# PHONE.net
KiCad netlist of a schematic drawn in EAGLE
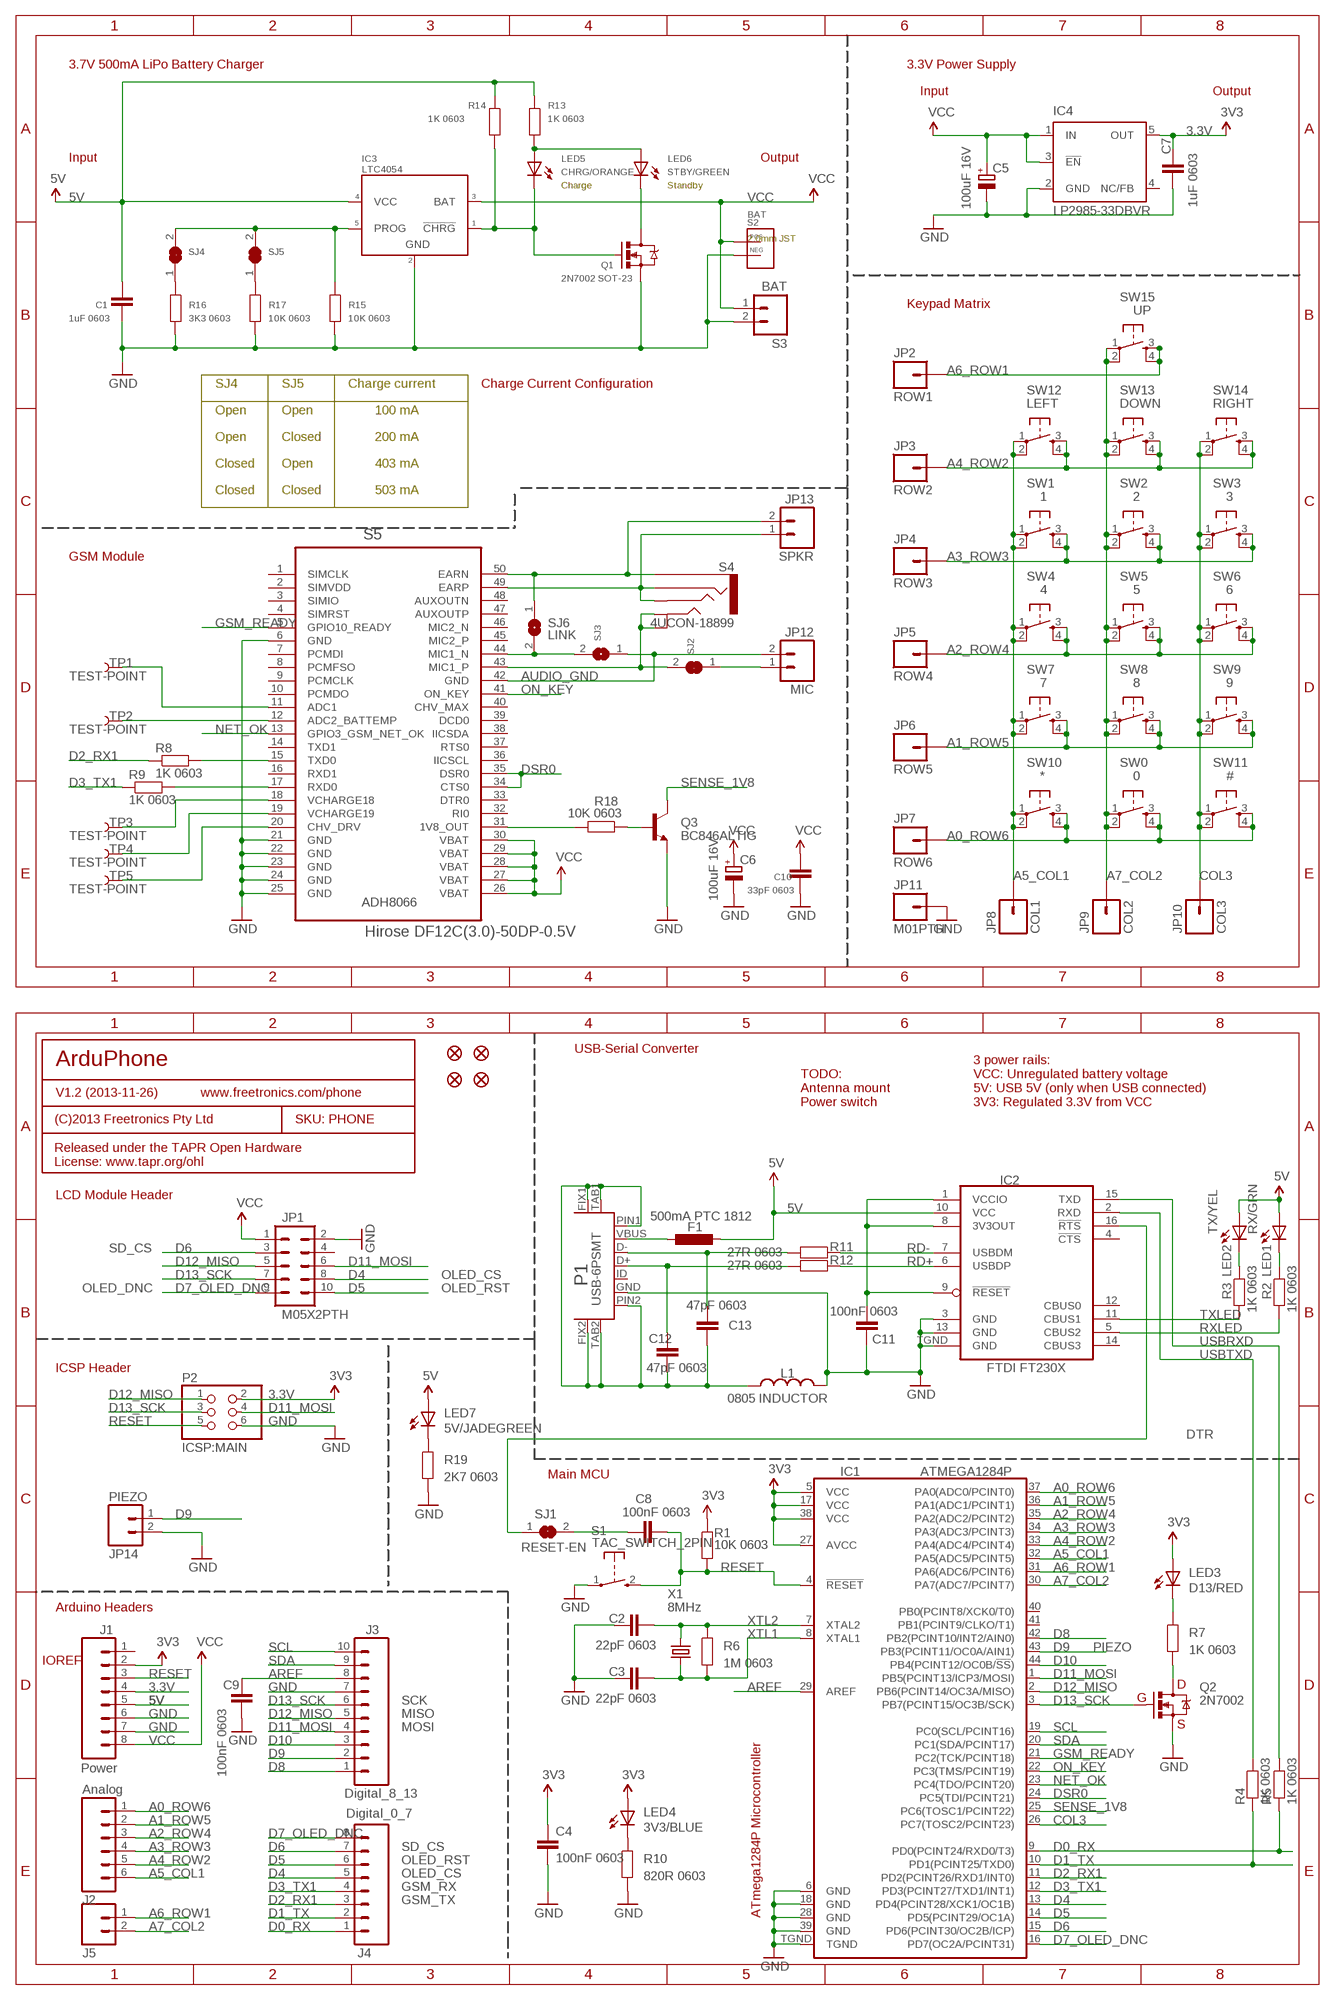
[diagram p0: schematic, sheet 1]

(export (version "E")
  (design (tool "Eeschema 10.0.6"))
  (components
    (comp (ref "C1")
      (value "1uF 0603")
      (footprint "eagle-import:0603")
      (libsource (lib "eagle-import") (part "freetronics-master-v1.1_CAP0603"))
    )
    (comp (ref "C2")
      (value "22pF 0603")
      (footprint "eagle-import:0603")
      (libsource (lib "eagle-import") (part "freetronics-master-v1.1_CAP0603"))
    )
    (comp (ref "C3")
      (value "22pF 0603")
      (footprint "eagle-import:0603")
      (libsource (lib "eagle-import") (part "freetronics-master-v1.1_CAP0603"))
    )
    (comp (ref "C4")
      (value "100nF 0603")
      (footprint "eagle-import:0603")
      (libsource (lib "eagle-import") (part "freetronics-master-v1.1_CAP0603"))
    )
    (comp (ref "C5")
      (value "100uF 16V")
      (footprint "eagle-import:PANASONIC_D")
      (libsource (lib "eagle-import") (part "CPOL-EUD"))
    )
    (comp (ref "C6")
      (value "100uF 16V")
      (footprint "eagle-import:PANASONIC_D")
      (libsource (lib "eagle-import") (part "CPOL-EUD"))
    )
    (comp (ref "C7")
      (value "1uF 0603")
      (footprint "eagle-import:0603")
      (libsource (lib "eagle-import") (part "freetronics-master-v1.1_CAP0603"))
    )
    (comp (ref "C8")
      (value "100nF 0603")
      (footprint "eagle-import:0603")
      (libsource (lib "eagle-import") (part "freetronics-master-v1.1_CAP0603"))
    )
    (comp (ref "C9")
      (value "100nF 0603")
      (footprint "eagle-import:0603")
      (libsource (lib "eagle-import") (part "freetronics-master-v1.1_CAP0603"))
    )
    (comp (ref "C10")
      (value "33pF 0603")
      (footprint "eagle-import:0603@1")
      (libsource (lib "eagle-import") (part "CAP0603"))
    )
    (comp (ref "C11")
      (value "100nF 0603")
      (footprint "eagle-import:0603")
      (libsource (lib "eagle-import") (part "freetronics-master-v1.1_CAP0603"))
    )
    (comp (ref "C12")
      (value "47pF 0603")
      (footprint "eagle-import:C0603")
      (libsource (lib "eagle-import") (part "C-EUC0603"))
    )
    (comp (ref "C13")
      (value "47pF 0603")
      (footprint "eagle-import:C0603")
      (libsource (lib "eagle-import") (part "C-EUC0603"))
    )
    (comp (ref "F1")
      (value "500mA PTC 1812")
      (footprint "eagle-import:L1812")
      (libsource (lib "eagle-import") (part "L-EUL1812"))
    )
    (comp (ref "IC1")
      (value "ATMEGA1284P")
      (footprint "eagle-import:QFN-44M1")
      (libsource (lib "eagle-import") (part "ATMEGA1284P"))
    )
    (comp (ref "IC2")
      (value "FT230X")
      (footprint "eagle-import:QFN-16")
      (libsource (lib "eagle-import") (part "FT230X"))
    )
    (comp (ref "IC3")
      (value "LTC4054")
      (footprint "eagle-import:SOT23-5")
      (libsource (lib "eagle-import") (part "LTC4054"))
    )
    (comp (ref "IC4")
      (value "LP2985-33DBVR")
      (footprint "eagle-import:TEXAS_SOT23-DBV")
      (libsource (lib "eagle-import") (part "TEXAS_TPS77033"))
    )
    (comp (ref "J1")
      (value "Power")
      (footprint "eagle-import:1X08")
      (libsource (lib "eagle-import") (part "M08"))
    )
    (comp (ref "J2")
      (value "Analog")
      (footprint "eagle-import:1X06")
      (libsource (lib "eagle-import") (part "M06SIP"))
    )
    (comp (ref "J3")
      (value "Digital_8_13")
      (footprint "eagle-import:1X10")
      (libsource (lib "eagle-import") (part "M100.1"))
    )
    (comp (ref "J4")
      (value "Digital_0_7")
      (footprint "eagle-import:1X08")
      (libsource (lib "eagle-import") (part "M08"))
    )
    (comp (ref "J5")
      (value "M02PTH")
      (footprint "eagle-import:1X02")
      (libsource (lib "eagle-import") (part "M02PTH"))
    )
    (comp (ref "JP1")
      (value "M05X2PTH")
      (footprint "eagle-import:AVR_ICSP")
      (libsource (lib "eagle-import") (part "M05X2PTH"))
    )
    (comp (ref "JP2")
      (value "ROW1")
      (footprint "eagle-import:1X01")
      (libsource (lib "eagle-import") (part "M01PTH"))
    )
    (comp (ref "JP3")
      (value "ROW2")
      (footprint "eagle-import:1X01")
      (libsource (lib "eagle-import") (part "M01PTH"))
    )
    (comp (ref "JP4")
      (value "ROW3")
      (footprint "eagle-import:1X01")
      (libsource (lib "eagle-import") (part "M01PTH"))
    )
    (comp (ref "JP5")
      (value "ROW4")
      (footprint "eagle-import:1X01")
      (libsource (lib "eagle-import") (part "M01PTH"))
    )
    (comp (ref "JP6")
      (value "ROW5")
      (footprint "eagle-import:1X01")
      (libsource (lib "eagle-import") (part "M01PTH"))
    )
    (comp (ref "JP7")
      (value "ROW6")
      (footprint "eagle-import:1X01")
      (libsource (lib "eagle-import") (part "M01PTH"))
    )
    (comp (ref "JP8")
      (value "COL1")
      (footprint "eagle-import:1X01")
      (libsource (lib "eagle-import") (part "M01PTH"))
    )
    (comp (ref "JP9")
      (value "COL2")
      (footprint "eagle-import:1X01")
      (libsource (lib "eagle-import") (part "M01PTH"))
    )
    (comp (ref "JP10")
      (value "COL3")
      (footprint "eagle-import:1X01")
      (libsource (lib "eagle-import") (part "M01PTH"))
    )
    (comp (ref "JP11")
      (value "M01PTH")
      (footprint "eagle-import:1X01")
      (libsource (lib "eagle-import") (part "freetronics-original_M01PTH"))
    )
    (comp (ref "JP12")
      (value "MIC")
      (footprint "eagle-import:1X02")
      (libsource (lib "eagle-import") (part "M02PTH"))
    )
    (comp (ref "JP13")
      (value "SPKR")
      (footprint "eagle-import:1X02")
      (libsource (lib "eagle-import") (part "M02PTH"))
    )
    (comp (ref "JP14")
      (value "PIEZO")
      (footprint "eagle-import:1X02")
      (libsource (lib "eagle-import") (part "M02PTH"))
    )
    (comp (ref "L1")
      (value "0805 INDUCTOR")
      (footprint "eagle-import:0805-LARGE")
      (libsource (lib "eagle-import") (part "INDUCTOR0805-LARGE"))
    )
    (comp (ref "LED1")
      (value "RX/GRN")
      (footprint "eagle-import:LED-0603")
      (libsource (lib "eagle-import") (part "LED0603"))
    )
    (comp (ref "LED2")
      (value "TX/YEL")
      (footprint "eagle-import:LED-0603")
      (libsource (lib "eagle-import") (part "LED0603"))
    )
    (comp (ref "LED3")
      (value "D13/RED")
      (footprint "eagle-import:LED-0603")
      (libsource (lib "eagle-import") (part "LED0603"))
    )
    (comp (ref "LED4")
      (value "3V3/BLUE")
      (footprint "eagle-import:LED-0603")
      (libsource (lib "eagle-import") (part "LED0603"))
    )
    (comp (ref "LED5")
      (value "CHRG/ORANGE")
      (footprint "eagle-import:LED-0603")
      (libsource (lib "eagle-import") (part "LED0603"))
    )
    (comp (ref "LED6")
      (value "STBY/GREEN")
      (footprint "eagle-import:LED-0603")
      (libsource (lib "eagle-import") (part "LED0603"))
    )
    (comp (ref "LED7")
      (value "5V/JADEGREEN")
      (footprint "eagle-import:LED-0603")
      (libsource (lib "eagle-import") (part "LED0603"))
    )
    (comp (ref "P1")
      (value "USB-6PSMT")
      (footprint "eagle-import:USB-MICROB-MB05PMXX")
      (libsource (lib "eagle-import") (part "USB-6PSMT"))
    )
    (comp (ref "P2")
      (value "ICSP:MAIN")
      (footprint "eagle-import:2X03")
      (libsource (lib "eagle-import") (part "PINHD-2X3"))
    )
    (comp (ref "Q1")
      (value "2N7002 SOT-23")
      (footprint "eagle-import:SOT23-3")
      (libsource (lib "eagle-import") (part "2N7002"))
    )
    (comp (ref "Q2")
      (value "2N7002")
      (footprint "eagle-import:SOT23-3")
      (libsource (lib "eagle-import") (part "MOSFET-NCHANNELSMD"))
    )
    (comp (ref "Q3")
      (value "BC846ALTIG")
      (footprint "eagle-import:SOT23-3")
      (libsource (lib "eagle-import") (part "TRANSISTOR_NPNSOT23-3"))
    )
    (comp (ref "R1")
      (value "10K 0603")
      (footprint "eagle-import:0603")
      (libsource (lib "eagle-import") (part "RESISTOR0603"))
    )
    (comp (ref "R2")
      (value "1K 0603")
      (footprint "eagle-import:0603")
      (libsource (lib "eagle-import") (part "RESISTOR0603"))
    )
    (comp (ref "R3")
      (value "1K 0603")
      (footprint "eagle-import:0603")
      (libsource (lib "eagle-import") (part "RESISTOR0603"))
    )
    (comp (ref "R4")
      (value "1K 0603")
      (footprint "eagle-import:0603")
      (libsource (lib "eagle-import") (part "RESISTOR0603"))
    )
    (comp (ref "R5")
      (value "1K 0603")
      (footprint "eagle-import:0603")
      (libsource (lib "eagle-import") (part "RESISTOR0603"))
    )
    (comp (ref "R6")
      (value "1M 0603")
      (footprint "eagle-import:0603")
      (libsource (lib "eagle-import") (part "RESISTOR0603"))
    )
    (comp (ref "R7")
      (value "1K 0603")
      (footprint "eagle-import:0603")
      (libsource (lib "eagle-import") (part "RESISTOR0603"))
    )
    (comp (ref "R8")
      (value "1K 0603")
      (footprint "eagle-import:0603")
      (libsource (lib "eagle-import") (part "RESISTOR0603"))
    )
    (comp (ref "R9")
      (value "1K 0603")
      (footprint "eagle-import:0603")
      (libsource (lib "eagle-import") (part "RESISTOR0603"))
    )
    (comp (ref "R10")
      (value "820R 0603")
      (footprint "eagle-import:0603")
      (libsource (lib "eagle-import") (part "RESISTOR0603"))
    )
    (comp (ref "R11")
      (value "27R 0603")
      (footprint "eagle-import:0603")
      (libsource (lib "eagle-import") (part "RESISTOR0603"))
    )
    (comp (ref "R12")
      (value "27R 0603")
      (footprint "eagle-import:0603")
      (libsource (lib "eagle-import") (part "RESISTOR0603"))
    )
    (comp (ref "R13")
      (value "1K 0603")
      (footprint "eagle-import:0603")
      (libsource (lib "eagle-import") (part "RESISTOR0603"))
    )
    (comp (ref "R14")
      (value "1K 0603")
      (footprint "eagle-import:0603")
      (libsource (lib "eagle-import") (part "RESISTOR0603"))
    )
    (comp (ref "R15")
      (value "10K 0603")
      (footprint "eagle-import:0603")
      (libsource (lib "eagle-import") (part "RESISTOR0603"))
    )
    (comp (ref "R16")
      (value "3K3 0603")
      (footprint "eagle-import:0603")
      (libsource (lib "eagle-import") (part "RESISTOR0603"))
    )
    (comp (ref "R17")
      (value "10K 0603")
      (footprint "eagle-import:0603")
      (libsource (lib "eagle-import") (part "RESISTOR0603"))
    )
    (comp (ref "R18")
      (value "10K 0603")
      (footprint "eagle-import:0603")
      (libsource (lib "eagle-import") (part "RESISTOR0603"))
    )
    (comp (ref "R19")
      (value "2K7 0603")
      (footprint "eagle-import:0603")
      (libsource (lib "eagle-import") (part "RESISTOR0603"))
    )
    (comp (ref "S1")
      (value "TAC_SWITCH_2PIN")
      (footprint "eagle-import:TACTILE_SWITCH_SMD_2PIN_TINY")
      (libsource (lib "eagle-import") (part "TAC_SWITCH_2PIN"))
    )
    (comp (ref "S2")
      (value "BAT")
      (footprint "eagle-import:JST-2MM-TH-RA")
      (libsource (lib "eagle-import") (part "2P-JST-TH-RAPTH"))
    )
    (comp (ref "S3")
      (value "BAT")
      (footprint "eagle-import:1X02")
      (libsource (lib "eagle-import") (part "M02PTH"))
    )
    (comp (ref "S4")
      (value "4UCON-18899")
      (footprint "eagle-import:4UCON-18899")
      (libsource (lib "eagle-import") (part "AUDIO-JACK-4POLE"))
    )
    (comp (ref "S5")
      (value "Hirose DF12C(3.0)-50DP-0.5V")
      (footprint "eagle-import:ADH8066")
      (libsource (lib "eagle-import") (part "ADH8066"))
    )
    (comp (ref "SJ1")
      (value "RESET-EN")
      (footprint "eagle-import:SJC")
      (libsource (lib "eagle-import") (part "SJCN"))
    )
    (comp (ref "SJ2")
      (value "SJCN")
      (footprint "eagle-import:SJC")
      (libsource (lib "eagle-import") (part "SJCN"))
    )
    (comp (ref "SJ3") (value "SJ") (footprint "eagle-import:SJ") (libsource (lib "eagle-import") (part "SJ")))
    (comp (ref "SJ4")
      (value "SJCN")
      (footprint "eagle-import:SJC")
      (libsource (lib "eagle-import") (part "SJCN"))
    )
    (comp (ref "SJ5")
      (value "SJCN")
      (footprint "eagle-import:SJC")
      (libsource (lib "eagle-import") (part "SJCN"))
    )
    (comp (ref "SJ6")
      (value "LINK")
      (footprint "eagle-import:SJ")
      (libsource (lib "eagle-import") (part "SJ"))
    )
    (comp (ref "SW0")
      (value "0")
      (footprint "eagle-import:TACTILE-PTH")
      (libsource (lib "eagle-import") (part "TAC_SWITCHPTH"))
    )
    (comp (ref "SW1")
      (value "1")
      (footprint "eagle-import:TACTILE-PTH")
      (libsource (lib "eagle-import") (part "TAC_SWITCHPTH"))
    )
    (comp (ref "SW2")
      (value "2")
      (footprint "eagle-import:TACTILE-PTH")
      (libsource (lib "eagle-import") (part "TAC_SWITCHPTH"))
    )
    (comp (ref "SW3")
      (value "3")
      (footprint "eagle-import:TACTILE-PTH")
      (libsource (lib "eagle-import") (part "TAC_SWITCHPTH"))
    )
    (comp (ref "SW4")
      (value "4")
      (footprint "eagle-import:TACTILE-PTH")
      (libsource (lib "eagle-import") (part "TAC_SWITCHPTH"))
    )
    (comp (ref "SW5")
      (value "5")
      (footprint "eagle-import:TACTILE-PTH")
      (libsource (lib "eagle-import") (part "TAC_SWITCHPTH"))
    )
    (comp (ref "SW6")
      (value "6")
      (footprint "eagle-import:TACTILE-PTH")
      (libsource (lib "eagle-import") (part "TAC_SWITCHPTH"))
    )
    (comp (ref "SW7")
      (value "7")
      (footprint "eagle-import:TACTILE-PTH")
      (libsource (lib "eagle-import") (part "TAC_SWITCHPTH"))
    )
    (comp (ref "SW8")
      (value "8")
      (footprint "eagle-import:TACTILE-PTH")
      (libsource (lib "eagle-import") (part "TAC_SWITCHPTH"))
    )
    (comp (ref "SW9")
      (value "9")
      (footprint "eagle-import:TACTILE-PTH")
      (libsource (lib "eagle-import") (part "TAC_SWITCHPTH"))
    )
    (comp (ref "SW10")
      (value "*")
      (footprint "eagle-import:TACTILE-PTH")
      (libsource (lib "eagle-import") (part "TAC_SWITCHPTH"))
    )
    (comp (ref "SW11")
      (value "#")
      (footprint "eagle-import:TACTILE-PTH")
      (libsource (lib "eagle-import") (part "TAC_SWITCHPTH"))
    )
    (comp (ref "SW12")
      (value "LEFT")
      (footprint "eagle-import:TACTILE-PTH")
      (libsource (lib "eagle-import") (part "TAC_SWITCHPTH"))
    )
    (comp (ref "SW13")
      (value "DOWN")
      (footprint "eagle-import:TACTILE-PTH")
      (libsource (lib "eagle-import") (part "TAC_SWITCHPTH"))
    )
    (comp (ref "SW14")
      (value "RIGHT")
      (footprint "eagle-import:TACTILE-PTH")
      (libsource (lib "eagle-import") (part "TAC_SWITCHPTH"))
    )
    (comp (ref "SW15")
      (value "UP")
      (footprint "eagle-import:TACTILE-PTH")
      (libsource (lib "eagle-import") (part "TAC_SWITCHPTH"))
    )
    (comp (ref "TP1")
      (value "TEST-POINT")
      (footprint "eagle-import:PAD.02X.02")
      (libsource (lib "eagle-import") (part "TEST-POINT2"))
    )
    (comp (ref "TP2")
      (value "TEST-POINT")
      (footprint "eagle-import:PAD.02X.02")
      (libsource (lib "eagle-import") (part "TEST-POINT2"))
    )
    (comp (ref "TP3")
      (value "TEST-POINT")
      (footprint "eagle-import:PAD.02X.02")
      (libsource (lib "eagle-import") (part "TEST-POINT2"))
    )
    (comp (ref "TP4")
      (value "TEST-POINT")
      (footprint "eagle-import:PAD.02X.02")
      (libsource (lib "eagle-import") (part "TEST-POINT2"))
    )
    (comp (ref "TP5")
      (value "TEST-POINT")
      (footprint "eagle-import:PAD.02X.02")
      (libsource (lib "eagle-import") (part "TEST-POINT2"))
    )
    (comp (ref "U$5")
      (value "FIDUCIAL1X2.5")
      (footprint "eagle-import:FIDUCIAL-1X2.5")
      (libsource (lib "eagle-import") (part "FIDUCIAL1X2.5"))
    )
    (comp (ref "U$6")
      (value "FIDUCIAL1X2.5")
      (footprint "eagle-import:FIDUCIAL-1X2.5")
      (libsource (lib "eagle-import") (part "FIDUCIAL1X2.5"))
    )
    (comp (ref "U$7")
      (value "FIDUCIAL1X2.5")
      (footprint "eagle-import:FIDUCIAL-1X2.5")
      (libsource (lib "eagle-import") (part "FIDUCIAL1X2.5"))
    )
    (comp (ref "U$14")
      (value "FIDUCIAL1X2.5")
      (footprint "eagle-import:FIDUCIAL-1X2.5")
      (libsource (lib "eagle-import") (part "FIDUCIAL1X2.5"))
    )
    (comp (ref "X1")
      (value "8MHz")
      (footprint "eagle-import:HC49U-V")
      (libsource (lib "eagle-import") (part "CRYSTALHC49UV"))
    )
  )
  (nets
    (net (code "1") (name "/A0_ROW6") (class "Default")
      (node (ref "IC1") (pin "37") (pinfunction "PA0(ADC0/PCINT0)_37") (pintype "bidirectional"))
      (node (ref "J2") (pin "1") (pinfunction "1_1") (pintype "passive"))
      (node (ref "JP7") (pin "1") (pinfunction "1_1") (pintype "passive"))
      (node (ref "SW0") (pin "3") (pinfunction "3_3") (pintype "passive"))
      (node (ref "SW0") (pin "4") (pinfunction "4_4") (pintype "passive"))
      (node (ref "SW10") (pin "3") (pinfunction "3_3") (pintype "passive"))
      (node (ref "SW10") (pin "4") (pinfunction "4_4") (pintype "passive"))
      (node (ref "SW11") (pin "3") (pinfunction "3_3") (pintype "passive"))
      (node (ref "SW11") (pin "4") (pinfunction "4_4") (pintype "passive"))
    )
    (net (code "2") (name "/A1_ROW5") (class "Default")
      (node (ref "IC1") (pin "36") (pinfunction "PA1(ADC1/PCINT1)_36") (pintype "bidirectional"))
      (node (ref "J2") (pin "2") (pinfunction "2_2") (pintype "passive"))
      (node (ref "JP6") (pin "1") (pinfunction "1_1") (pintype "passive"))
      (node (ref "SW7") (pin "3") (pinfunction "3_3") (pintype "passive"))
      (node (ref "SW7") (pin "4") (pinfunction "4_4") (pintype "passive"))
      (node (ref "SW8") (pin "3") (pinfunction "3_3") (pintype "passive"))
      (node (ref "SW8") (pin "4") (pinfunction "4_4") (pintype "passive"))
      (node (ref "SW9") (pin "3") (pinfunction "3_3") (pintype "passive"))
      (node (ref "SW9") (pin "4") (pinfunction "4_4") (pintype "passive"))
    )
    (net (code "3") (name "/A2_ROW4") (class "Default")
      (node (ref "IC1") (pin "35") (pinfunction "PA2(ADC2/PCINT2)_35") (pintype "bidirectional"))
      (node (ref "J2") (pin "3") (pinfunction "3_3") (pintype "passive"))
      (node (ref "JP5") (pin "1") (pinfunction "1_1") (pintype "passive"))
      (node (ref "SW4") (pin "3") (pinfunction "3_3") (pintype "passive"))
      (node (ref "SW4") (pin "4") (pinfunction "4_4") (pintype "passive"))
      (node (ref "SW5") (pin "3") (pinfunction "3_3") (pintype "passive"))
      (node (ref "SW5") (pin "4") (pinfunction "4_4") (pintype "passive"))
      (node (ref "SW6") (pin "3") (pinfunction "3_3") (pintype "passive"))
      (node (ref "SW6") (pin "4") (pinfunction "4_4") (pintype "passive"))
    )
    (net (code "4") (name "/A3_ROW3") (class "Default")
      (node (ref "IC1") (pin "34") (pinfunction "PA3(ADC3/PCINT3)_34") (pintype "bidirectional"))
      (node (ref "J2") (pin "4") (pinfunction "4_4") (pintype "passive"))
      (node (ref "JP4") (pin "1") (pinfunction "1_1") (pintype "passive"))
      (node (ref "SW1") (pin "3") (pinfunction "3_3") (pintype "passive"))
      (node (ref "SW1") (pin "4") (pinfunction "4_4") (pintype "passive"))
      (node (ref "SW2") (pin "3") (pinfunction "3_3") (pintype "passive"))
      (node (ref "SW2") (pin "4") (pinfunction "4_4") (pintype "passive"))
      (node (ref "SW3") (pin "3") (pinfunction "3_3") (pintype "passive"))
      (node (ref "SW3") (pin "4") (pinfunction "4_4") (pintype "passive"))
    )
    (net (code "5") (name "/A4_ROW2") (class "Default")
      (node (ref "IC1") (pin "33") (pinfunction "PA4(ADC4/PCINT4)_33") (pintype "bidirectional"))
      (node (ref "J2") (pin "5") (pinfunction "5_5") (pintype "passive"))
      (node (ref "JP3") (pin "1") (pinfunction "1_1") (pintype "passive"))
      (node (ref "SW12") (pin "3") (pinfunction "3_3") (pintype "passive"))
      (node (ref "SW12") (pin "4") (pinfunction "4_4") (pintype "passive"))
      (node (ref "SW13") (pin "3") (pinfunction "3_3") (pintype "passive"))
      (node (ref "SW13") (pin "4") (pinfunction "4_4") (pintype "passive"))
      (node (ref "SW14") (pin "3") (pinfunction "3_3") (pintype "passive"))
      (node (ref "SW14") (pin "4") (pinfunction "4_4") (pintype "passive"))
    )
    (net (code "6") (name "/A5_COL1") (class "Default")
      (node (ref "IC1") (pin "32") (pinfunction "PA5(ADC5/PCINT5)_32") (pintype "bidirectional"))
      (node (ref "J2") (pin "6") (pinfunction "6_6") (pintype "passive"))
      (node (ref "JP8") (pin "1") (pinfunction "1_1") (pintype "passive"))
      (node (ref "SW1") (pin "1") (pinfunction "1_1") (pintype "passive"))
      (node (ref "SW1") (pin "2") (pinfunction "2_2") (pintype "passive"))
      (node (ref "SW10") (pin "1") (pinfunction "1_1") (pintype "passive"))
      (node (ref "SW10") (pin "2") (pinfunction "2_2") (pintype "passive"))
      (node (ref "SW12") (pin "1") (pinfunction "1_1") (pintype "passive"))
      (node (ref "SW12") (pin "2") (pinfunction "2_2") (pintype "passive"))
      (node (ref "SW4") (pin "1") (pinfunction "1_1") (pintype "passive"))
      (node (ref "SW4") (pin "2") (pinfunction "2_2") (pintype "passive"))
      (node (ref "SW7") (pin "1") (pinfunction "1_1") (pintype "passive"))
      (node (ref "SW7") (pin "2") (pinfunction "2_2") (pintype "passive"))
    )
    (net (code "7") (name "/A6_ROW1") (class "Default")
      (node (ref "IC1") (pin "31") (pinfunction "PA6(ADC6/PCINT6)_31") (pintype "bidirectional"))
      (node (ref "J5") (pin "1") (pinfunction "1_1") (pintype "passive"))
      (node (ref "JP2") (pin "1") (pinfunction "1_1") (pintype "passive"))
      (node (ref "SW15") (pin "3") (pinfunction "3_3") (pintype "passive"))
      (node (ref "SW15") (pin "4") (pinfunction "4_4") (pintype "passive"))
    )
    (net (code "8") (name "/A7_COL2") (class "Default")
      (node (ref "IC1") (pin "30") (pinfunction "PA7(ADC7/PCINT7)_30") (pintype "bidirectional"))
      (node (ref "J5") (pin "2") (pinfunction "2_2") (pintype "passive"))
      (node (ref "JP9") (pin "1") (pinfunction "1_1") (pintype "passive"))
      (node (ref "SW0") (pin "1") (pinfunction "1_1") (pintype "passive"))
      (node (ref "SW0") (pin "2") (pinfunction "2_2") (pintype "passive"))
      (node (ref "SW13") (pin "1") (pinfunction "1_1") (pintype "passive"))
      (node (ref "SW13") (pin "2") (pinfunction "2_2") (pintype "passive"))
      (node (ref "SW15") (pin "1") (pinfunction "1_1") (pintype "passive"))
      (node (ref "SW15") (pin "2") (pinfunction "2_2") (pintype "passive"))
      (node (ref "SW2") (pin "1") (pinfunction "1_1") (pintype "passive"))
      (node (ref "SW2") (pin "2") (pinfunction "2_2") (pintype "passive"))
      (node (ref "SW5") (pin "1") (pinfunction "1_1") (pintype "passive"))
      (node (ref "SW5") (pin "2") (pinfunction "2_2") (pintype "passive"))
      (node (ref "SW8") (pin "1") (pinfunction "1_1") (pintype "passive"))
      (node (ref "SW8") (pin "2") (pinfunction "2_2") (pintype "passive"))
    )
    (net (code "9") (name "/AREF") (class "Default")
      (node (ref "C9") (pin "1") (pinfunction "1_1") (pintype "passive"))
      (node (ref "IC1") (pin "29") (pinfunction "AREF_29") (pintype "bidirectional"))
      (node (ref "J3") (pin "8") (pinfunction "8_8") (pintype "passive"))
    )
    (net (code "10") (name "/AUDIO_GND") (class "Default")
      (node (ref "JP12") (pin "2") (pinfunction "2_2") (pintype "passive"))
      (node (ref "S5") (pin "42") (pinfunction "GND_42") (pintype "passive"))
      (node (ref "SJ3") (pin "1") (pinfunction "1_1") (pintype "passive"))
    )
    (net (code "11") (name "/COL3") (class "Default")
      (node (ref "IC1") (pin "26") (pinfunction "PC7(TOSC2/PCINT23)_26") (pintype "bidirectional"))
      (node (ref "JP10") (pin "1") (pinfunction "1_1") (pintype "passive"))
      (node (ref "SW11") (pin "1") (pinfunction "1_1") (pintype "passive"))
      (node (ref "SW11") (pin "2") (pinfunction "2_2") (pintype "passive"))
      (node (ref "SW14") (pin "1") (pinfunction "1_1") (pintype "passive"))
      (node (ref "SW14") (pin "2") (pinfunction "2_2") (pintype "passive"))
      (node (ref "SW3") (pin "1") (pinfunction "1_1") (pintype "passive"))
      (node (ref "SW3") (pin "2") (pinfunction "2_2") (pintype "passive"))
      (node (ref "SW6") (pin "1") (pinfunction "1_1") (pintype "passive"))
      (node (ref "SW6") (pin "2") (pinfunction "2_2") (pintype "passive"))
      (node (ref "SW9") (pin "1") (pinfunction "1_1") (pintype "passive"))
      (node (ref "SW9") (pin "2") (pinfunction "2_2") (pintype "passive"))
    )
    (net (code "12") (name "/D0_RX") (class "Default")
      (node (ref "IC1") (pin "9") (pinfunction "PD0(PCINT24/RXD0/T3)_9") (pintype "bidirectional"))
      (node (ref "J4") (pin "1") (pinfunction "1_1") (pintype "passive"))
      (node (ref "R5") (pin "1") (pinfunction "1_1") (pintype "passive"))
    )
    (net (code "13") (name "/D1_TX") (class "Default")
      (node (ref "IC1") (pin "10") (pinfunction "PD1(PCINT25/TXD0)_10") (pintype "bidirectional"))
      (node (ref "J4") (pin "2") (pinfunction "2_2") (pintype "passive"))
      (node (ref "R4") (pin "1") (pinfunction "1_1") (pintype "passive"))
    )
    (net (code "14") (name "/D2_RX1") (class "Default")
      (node (ref "IC1") (pin "11") (pinfunction "PD2(PCINT26/RXD1/INT0)_11") (pintype "bidirectional"))
      (node (ref "J4") (pin "3") (pinfunction "3_3") (pintype "passive"))
      (node (ref "R8") (pin "1") (pinfunction "1_1") (pintype "passive"))
    )
    (net (code "15") (name "/D3_TX1") (class "Default")
      (node (ref "IC1") (pin "12") (pinfunction "PD3(PCINT27/TXD1/INT1)_12") (pintype "bidirectional"))
      (node (ref "J4") (pin "4") (pinfunction "4_4") (pintype "passive"))
      (node (ref "R9") (pin "1") (pinfunction "1_1") (pintype "passive"))
    )
    (net (code "16") (name "/D4") (class "Default")
      (node (ref "IC1") (pin "13") (pinfunction "PD4(PCINT28/XCK1/OC1B)_13") (pintype "bidirectional"))
      (node (ref "J4") (pin "5") (pinfunction "5_5") (pintype "passive"))
      (node (ref "JP1") (pin "8") (pinfunction "8_8") (pintype "passive"))
    )
    (net (code "17") (name "/D5") (class "Default")
      (node (ref "IC1") (pin "14") (pinfunction "PD5(PCINT29/OC1A)_14") (pintype "bidirectional"))
      (node (ref "J4") (pin "6") (pinfunction "6_6") (pintype "passive"))
      (node (ref "JP1") (pin "10") (pinfunction "10_10") (pintype "passive"))
    )
    (net (code "18") (name "/D6") (class "Default")
      (node (ref "IC1") (pin "15") (pinfunction "PD6(PCINT30/OC2B/ICP)_15") (pintype "bidirectional"))
      (node (ref "J4") (pin "7") (pinfunction "7_7") (pintype "passive"))
      (node (ref "JP1") (pin "3") (pinfunction "3_3") (pintype "passive"))
    )
    (net (code "19") (name "/D7_OLED_DNC") (class "Default")
      (node (ref "IC1") (pin "16") (pinfunction "PD7(OC2A/PCINT31)_16") (pintype "bidirectional"))
      (node (ref "J4") (pin "8") (pinfunction "8_8") (pintype "passive"))
      (node (ref "JP1") (pin "9") (pinfunction "9_9") (pintype "passive"))
    )
    (net (code "20") (name "/D8") (class "Default")
      (node (ref "IC1") (pin "42") (pinfunction "PB2(PCINT10/INT2/AIN0)_42") (pintype "bidirectional"))
      (node (ref "J3") (pin "1") (pinfunction "1_1") (pintype "passive"))
    )
    (net (code "21") (name "/D9") (class "Default")
      (node (ref "IC1") (pin "43") (pinfunction "PB3(PCINT11/OC0A/AIN1)_43") (pintype "bidirectional"))
      (node (ref "J3") (pin "2") (pinfunction "2_2") (pintype "passive"))
      (node (ref "JP14") (pin "1") (pinfunction "1_1") (pintype "passive"))
    )
    (net (code "22") (name "/D10") (class "Default")
      (node (ref "IC1") (pin "44") (pinfunction "PB4(PCINT12/OC0B/~{SS})_44") (pintype "bidirectional"))
      (node (ref "J3") (pin "3") (pinfunction "3_3") (pintype "passive"))
    )
    (net (code "23") (name "/D11_MOSI") (class "Default")
      (node (ref "IC1") (pin "1") (pinfunction "PB5(PCINT13/ICP3/MOSI)_1") (pintype "bidirectional"))
      (node (ref "J3") (pin "4") (pinfunction "4_4") (pintype "passive"))
      (node (ref "JP1") (pin "6") (pinfunction "6_6") (pintype "passive"))
      (node (ref "P2") (pin "4") (pinfunction "4_4") (pintype "passive"))
    )
    (net (code "24") (name "/D12_MISO") (class "Default")
      (node (ref "IC1") (pin "2") (pinfunction "PB6(PCINT14/OC3A/MISO)_2") (pintype "bidirectional"))
      (node (ref "J3") (pin "5") (pinfunction "5_5") (pintype "passive"))
      (node (ref "JP1") (pin "5") (pinfunction "5_5") (pintype "passive"))
      (node (ref "P2") (pin "1") (pinfunction "1_1") (pintype "passive"))
    )
    (net (code "25") (name "/D13_SCK") (class "Default")
      (node (ref "IC1") (pin "3") (pinfunction "PB7(PCINT15/OC3B/SCK)_3") (pintype "bidirectional"))
      (node (ref "J3") (pin "6") (pinfunction "6_6") (pintype "passive"))
      (node (ref "JP1") (pin "7") (pinfunction "7_7") (pintype "passive"))
      (node (ref "P2") (pin "3") (pinfunction "3_3") (pintype "passive"))
      (node (ref "Q2") (pin "1") (pinfunction "G_1") (pintype "passive"))
    )
    (net (code "26") (name "/DSR0") (class "Default")
      (node (ref "IC1") (pin "24") (pinfunction "PC5(TDI/PCINT21)_24") (pintype "bidirectional"))
      (node (ref "S5") (pin "34") (pinfunction "CTS0_34") (pintype "passive"))
      (node (ref "S5") (pin "35") (pinfunction "DSR0_35") (pintype "passive"))
    )
    (net (code "27") (name "/DTR") (class "Default")
      (node (ref "IC2") (pin "16") (pinfunction "~{RTS}_16") (pintype "bidirectional"))
      (node (ref "SJ1") (pin "1") (pinfunction "1_1") (pintype "passive"))
    )
    (net (code "28") (name "/GSM_READY") (class "Default")
      (node (ref "IC1") (pin "21") (pinfunction "PC2(TCK/PCINT18)_21") (pintype "bidirectional"))
      (node (ref "S5") (pin "5") (pinfunction "GPIO10_READY_5") (pintype "passive"))
    )
    (net (code "29") (name "/NET_OK") (class "Default")
      (node (ref "IC1") (pin "23") (pinfunction "PC4(TDO/PCINT20)_23") (pintype "bidirectional"))
      (node (ref "S5") (pin "13") (pinfunction "GPIO3_GSM_NET_OK_13") (pintype "passive"))
    )
    (net (code "30") (name "/ON_KEY") (class "Default")
      (node (ref "IC1") (pin "22") (pinfunction "PC3(TMS/PCINT19)_22") (pintype "bidirectional"))
      (node (ref "S5") (pin "41") (pinfunction "ON_KEY_41") (pintype "passive"))
    )
    (net (code "31") (name "/RD+") (class "Default")
      (node (ref "IC2") (pin "6") (pinfunction "USBDP_6") (pintype "bidirectional"))
      (node (ref "R12") (pin "1") (pinfunction "1_1") (pintype "passive"))
    )
    (net (code "32") (name "/RD-") (class "Default")
      (node (ref "IC2") (pin "7") (pinfunction "USBDM_7") (pintype "bidirectional"))
      (node (ref "R11") (pin "1") (pinfunction "1_1") (pintype "passive"))
    )
    (net (code "33") (name "/RESET") (class "Default")
      (node (ref "C8") (pin "2") (pinfunction "2_2") (pintype "passive"))
      (node (ref "IC1") (pin "4") (pinfunction "~{RESET}_4") (pintype "bidirectional"))
      (node (ref "J1") (pin "3") (pinfunction "3_3") (pintype "passive"))
      (node (ref "P2") (pin "5") (pinfunction "5_5") (pintype "passive"))
      (node (ref "R1") (pin "1") (pinfunction "1_1") (pintype "passive"))
      (node (ref "S1") (pin "2") (pinfunction "S_2") (pintype "passive"))
    )
    (net (code "34") (name "/RXLED") (class "Default")
      (node (ref "IC2") (pin "5") (pinfunction "CBUS2_5") (pintype "bidirectional"))
      (node (ref "R2") (pin "1") (pinfunction "1_1") (pintype "passive"))
    )
    (net (code "35") (name "/SCL") (class "Default")
      (node (ref "IC1") (pin "19") (pinfunction "PC0(SCL/PCINT16)_19") (pintype "bidirectional"))
      (node (ref "J3") (pin "10") (pinfunction "10_10") (pintype "passive"))
    )
    (net (code "36") (name "/SDA") (class "Default")
      (node (ref "IC1") (pin "20") (pinfunction "PC1(SDA/PCINT17)_20") (pintype "bidirectional"))
      (node (ref "J3") (pin "9") (pinfunction "9_9") (pintype "passive"))
    )
    (net (code "37") (name "/SENSE_1V8") (class "Default")
      (node (ref "IC1") (pin "25") (pinfunction "PC6(TOSC1/PCINT22)_25") (pintype "bidirectional"))
      (node (ref "Q3") (pin "3") (pinfunction "C_3") (pintype "passive"))
    )
    (net (code "38") (name "/TXLED") (class "Default")
      (node (ref "IC2") (pin "11") (pinfunction "CBUS1_11") (pintype "bidirectional"))
      (node (ref "R3") (pin "1") (pinfunction "1_1") (pintype "passive"))
    )
    (net (code "39") (name "/USBRXD") (class "Default")
      (node (ref "IC2") (pin "15") (pinfunction "TXD_15") (pintype "bidirectional"))
      (node (ref "R5") (pin "2") (pinfunction "2_2") (pintype "passive"))
    )
    (net (code "40") (name "/USBTXD") (class "Default")
      (node (ref "IC2") (pin "2") (pinfunction "RXD_2") (pintype "bidirectional"))
      (node (ref "R4") (pin "2") (pinfunction "2_2") (pintype "passive"))
    )
    (net (code "41") (name "/XTL1") (class "Default")
      (node (ref "C3") (pin "2") (pinfunction "2_2") (pintype "passive"))
      (node (ref "IC1") (pin "8") (pinfunction "XTAL1_8") (pintype "bidirectional"))
      (node (ref "R6") (pin "1") (pinfunction "1_1") (pintype "passive"))
      (node (ref "X1") (pin "1") (pinfunction "1_1") (pintype "passive"))
    )
    (net (code "42") (name "/XTL2") (class "Default")
      (node (ref "C2") (pin "2") (pinfunction "2_2") (pintype "passive"))
      (node (ref "IC1") (pin "7") (pinfunction "XTAL2_7") (pintype "bidirectional"))
      (node (ref "R6") (pin "2") (pinfunction "2_2") (pintype "passive"))
      (node (ref "X1") (pin "2") (pinfunction "2_2") (pintype "passive"))
    )
    (net (code "43") (name "3V3") (class "Default")
      (node (ref "C4") (pin "1") (pinfunction "1_1") (pintype "passive"))
      (node (ref "C7") (pin "2") (pinfunction "2_2") (pintype "passive"))
      (node (ref "IC1") (pin "17") (pinfunction "VCC_17") (pintype "bidirectional"))
      (node (ref "IC1") (pin "27") (pinfunction "AVCC_27") (pintype "bidirectional"))
      (node (ref "IC1") (pin "38") (pinfunction "VCC_38") (pintype "bidirectional"))
      (node (ref "IC1") (pin "5") (pinfunction "VCC_5") (pintype "bidirectional"))
      (node (ref "IC4") (pin "5") (pinfunction "OUT_5") (pintype "passive"))
      (node (ref "J1") (pin "2") (pinfunction "2_2") (pintype "passive"))
      (node (ref "J1") (pin "4") (pinfunction "4_4") (pintype "passive"))
      (node (ref "LED3") (pin "A") (pinfunction "A_A") (pintype "passive"))
      (node (ref "LED4") (pin "A") (pinfunction "A_A") (pintype "passive"))
      (node (ref "P2") (pin "2") (pinfunction "2_2") (pintype "passive"))
      (node (ref "R1") (pin "2") (pinfunction "2_2") (pintype "passive"))
    )
    (net (code "44") (name "5V") (class "Default")
      (node (ref "C1") (pin "2") (pinfunction "2_2") (pintype "passive"))
      (node (ref "F1") (pin "2") (pinfunction "2_2") (pintype "passive"))
      (node (ref "IC2") (pin "10") (pinfunction "VCC_10") (pintype "power_in"))
      (node (ref "IC3") (pin "4") (pinfunction "VCC_4") (pintype "bidirectional"))
      (node (ref "J1") (pin "5") (pinfunction "5_5") (pintype "passive"))
      (node (ref "LED1") (pin "A") (pinfunction "A_A") (pintype "passive"))
      (node (ref "LED2") (pin "A") (pinfunction "A_A") (pintype "passive"))
      (node (ref "LED7") (pin "A") (pinfunction "A_A") (pintype "passive"))
      (node (ref "R13") (pin "1") (pinfunction "1_1") (pintype "passive"))
      (node (ref "R14") (pin "1") (pinfunction "1_1") (pintype "passive"))
    )
    (net (code "45") (name "GND") (class "Default")
      (node (ref "C1") (pin "1") (pinfunction "1_1") (pintype "passive"))
      (node (ref "C10") (pin "1") (pinfunction "1_1") (pintype "passive"))
      (node (ref "C11") (pin "2") (pinfunction "2_2") (pintype "passive"))
      (node (ref "C2") (pin "1") (pinfunction "1_1") (pintype "passive"))
      (node (ref "C3") (pin "1") (pinfunction "1_1") (pintype "passive"))
      (node (ref "C4") (pin "2") (pinfunction "2_2") (pintype "passive"))
      (node (ref "C5") (pin "-") (pinfunction "-_-") (pintype "passive"))
      (node (ref "C6") (pin "-") (pinfunction "-_-") (pintype "passive"))
      (node (ref "C7") (pin "1") (pinfunction "1_1") (pintype "passive"))
      (node (ref "C9") (pin "2") (pinfunction "2_2") (pintype "passive"))
      (node (ref "IC1") (pin "18") (pinfunction "GND_18") (pintype "bidirectional"))
      (node (ref "IC1") (pin "28") (pinfunction "GND_28") (pintype "bidirectional"))
      (node (ref "IC1") (pin "39") (pinfunction "GND_39") (pintype "bidirectional"))
      (node (ref "IC1") (pin "6") (pinfunction "GND_6") (pintype "bidirectional"))
      (node (ref "IC1") (pin "TGND") (pinfunction "TGND_TGND") (pintype "bidirectional"))
      (node (ref "IC2") (pin "13") (pinfunction "GND_13") (pintype "bidirectional"))
      (node (ref "IC2") (pin "3") (pinfunction "GND_3") (pintype "bidirectional"))
      (node (ref "IC2") (pin "TGND") (pinfunction "GND_TGND") (pintype "bidirectional"))
      (node (ref "IC3") (pin "2") (pinfunction "GND_2") (pintype "bidirectional"))
      (node (ref "IC4") (pin "2") (pinfunction "GND_2") (pintype "power_in"))
      (node (ref "J1") (pin "6") (pinfunction "6_6") (pintype "passive"))
      (node (ref "J1") (pin "7") (pinfunction "7_7") (pintype "passive"))
      (node (ref "J3") (pin "7") (pinfunction "7_7") (pintype "passive"))
      (node (ref "JP1") (pin "2") (pinfunction "2_2") (pintype "passive"))
      (node (ref "JP11") (pin "1") (pinfunction "1_1") (pintype "passive"))
      (node (ref "JP14") (pin "2") (pinfunction "2_2") (pintype "passive"))
      (node (ref "L1") (pin "2") (pinfunction "2_2") (pintype "passive"))
      (node (ref "P1") (pin "GND") (pinfunction "GND_GND") (pintype "bidirectional"))
      (node (ref "P2") (pin "6") (pinfunction "6_6") (pintype "passive"))
      (node (ref "Q1") (pin "2") (pinfunction "S_2") (pintype "passive"))
      (node (ref "Q2") (pin "2") (pinfunction "S_2") (pintype "passive"))
      (node (ref "Q3") (pin "2") (pinfunction "E_2") (pintype "passive"))
      (node (ref "R10") (pin "1") (pinfunction "1_1") (pintype "passive"))
      (node (ref "R15") (pin "2") (pinfunction "2_2") (pintype "passive"))
      (node (ref "R16") (pin "2") (pinfunction "2_2") (pintype "passive"))
      (node (ref "R17") (pin "2") (pinfunction "2_2") (pintype "passive"))
      (node (ref "R19") (pin "1") (pinfunction "1_1") (pintype "passive"))
      (node (ref "S1") (pin "1") (pinfunction "P_1") (pintype "passive"))
      (node (ref "S2") (pin "NEG") (pinfunction "NEG_NEG") (pintype "power_in"))
      (node (ref "S3") (pin "2") (pinfunction "2_2") (pintype "passive"))
      (node (ref "S5") (pin "21") (pinfunction "GND_21") (pintype "passive"))
      (node (ref "S5") (pin "22") (pinfunction "GND_22") (pintype "passive"))
      (node (ref "S5") (pin "23") (pinfunction "GND_23") (pintype "passive"))
      (node (ref "S5") (pin "24") (pinfunction "GND_24") (pintype "passive"))
      (node (ref "S5") (pin "25") (pinfunction "GND_25") (pintype "passive"))
      (node (ref "S5") (pin "6") (pinfunction "GND_6") (pintype "passive"))
    )
    (net (code "46") (name "Net-(C8-Pad1)") (class "Default")
      (node (ref "C8") (pin "1") (pinfunction "1_1") (pintype "passive"))
      (node (ref "SJ1") (pin "2") (pinfunction "2_2") (pintype "passive"))
    )
    (net (code "47") (name "Net-(C12-Pad1)") (class "Default")
      (node (ref "C12") (pin "1") (pinfunction "1_1") (pintype "passive"))
      (node (ref "P1") (pin "D+") (pinfunction "D+_D+") (pintype "bidirectional"))
      (node (ref "R12") (pin "2") (pinfunction "2_2") (pintype "passive"))
    )
    (net (code "48") (name "Net-(C12-Pad2)") (class "Default")
      (node (ref "C12") (pin "2") (pinfunction "2_2") (pintype "passive"))
      (node (ref "C13") (pin "2") (pinfunction "2_2") (pintype "passive"))
      (node (ref "L1") (pin "1") (pinfunction "1_1") (pintype "passive"))
      (node (ref "P1") (pin "FIX1") (pinfunction "FIX1_FIX1") (pintype "bidirectional"))
      (node (ref "P1") (pin "FIX2") (pinfunction "FIX2_FIX2") (pintype "bidirectional"))
      (node (ref "P1") (pin "PIN1") (pinfunction "PIN1_PIN1") (pintype "bidirectional"))
      (node (ref "P1") (pin "PIN2") (pinfunction "PIN2_PIN2") (pintype "bidirectional"))
      (node (ref "P1") (pin "TAB1") (pinfunction "TAB1_TAB1") (pintype "bidirectional"))
      (node (ref "P1") (pin "TAB2") (pinfunction "TAB2_TAB2") (pintype "bidirectional"))
    )
    (net (code "49") (name "Net-(C13-Pad1)") (class "Default")
      (node (ref "C13") (pin "1") (pinfunction "1_1") (pintype "passive"))
      (node (ref "P1") (pin "D-") (pinfunction "D-_D-") (pintype "bidirectional"))
      (node (ref "R11") (pin "2") (pinfunction "2_2") (pintype "passive"))
    )
    (net (code "50") (name "Net-(F1-Pad1)") (class "Default")
      (node (ref "F1") (pin "1") (pinfunction "1_1") (pintype "passive"))
      (node (ref "P1") (pin "VBUS") (pinfunction "VBUS_VBUS") (pintype "bidirectional"))
    )
    (net (code "51") (name "Net-(IC2-3V3OUT)") (class "Default")
      (node (ref "C11") (pin "1") (pinfunction "1_1") (pintype "passive"))
      (node (ref "IC2") (pin "1") (pinfunction "VCCIO_1") (pintype "power_in"))
      (node (ref "IC2") (pin "8") (pinfunction "3V3OUT_8") (pintype "power_in"))
      (node (ref "IC2") (pin "9") (pinfunction "~{RESET}_9") (pintype "input"))
    )
    (net (code "52") (name "Net-(IC3-PROG)") (class "Default")
      (node (ref "IC3") (pin "5") (pinfunction "PROG_5") (pintype "bidirectional"))
      (node (ref "R15") (pin "1") (pinfunction "1_1") (pintype "passive"))
      (node (ref "SJ4") (pin "2") (pinfunction "2_2") (pintype "passive"))
      (node (ref "SJ5") (pin "2") (pinfunction "2_2") (pintype "passive"))
    )
    (net (code "53") (name "Net-(IC3-~{CHRG})") (class "Default")
      (node (ref "IC3") (pin "1") (pinfunction "~{CHRG}_1") (pintype "bidirectional"))
      (node (ref "LED5") (pin "C") (pinfunction "C_C") (pintype "passive"))
      (node (ref "Q1") (pin "1") (pinfunction "G_1") (pintype "passive"))
      (node (ref "R14") (pin "2") (pinfunction "2_2") (pintype "passive"))
    )
    (net (code "54") (name "Net-(JP12-Pad1)") (class "Default")
      (node (ref "JP12") (pin "1") (pinfunction "1_1") (pintype "passive"))
      (node (ref "SJ2") (pin "1") (pinfunction "1_1") (pintype "passive"))
    )
    (net (code "55") (name "Net-(LED1-PadC)") (class "Default")
      (node (ref "LED1") (pin "C") (pinfunction "C_C") (pintype "passive"))
      (node (ref "R2") (pin "2") (pinfunction "2_2") (pintype "passive"))
    )
    (net (code "56") (name "Net-(LED2-PadC)") (class "Default")
      (node (ref "LED2") (pin "C") (pinfunction "C_C") (pintype "passive"))
      (node (ref "R3") (pin "2") (pinfunction "2_2") (pintype "passive"))
    )
    (net (code "57") (name "Net-(LED3-PadC)") (class "Default")
      (node (ref "LED3") (pin "C") (pinfunction "C_C") (pintype "passive"))
      (node (ref "R7") (pin "2") (pinfunction "2_2") (pintype "passive"))
    )
    (net (code "58") (name "Net-(LED4-PadC)") (class "Default")
      (node (ref "LED4") (pin "C") (pinfunction "C_C") (pintype "passive"))
      (node (ref "R10") (pin "2") (pinfunction "2_2") (pintype "passive"))
    )
    (net (code "59") (name "Net-(LED5-PadA)") (class "Default")
      (node (ref "LED5") (pin "A") (pinfunction "A_A") (pintype "passive"))
      (node (ref "LED6") (pin "A") (pinfunction "A_A") (pintype "passive"))
      (node (ref "R13") (pin "2") (pinfunction "2_2") (pintype "passive"))
    )
    (net (code "60") (name "Net-(LED7-PadC)") (class "Default")
      (node (ref "LED7") (pin "C") (pinfunction "C_C") (pintype "passive"))
      (node (ref "R19") (pin "2") (pinfunction "2_2") (pintype "passive"))
    )
    (net (code "61") (name "Net-(Q1-D)") (class "Default")
      (node (ref "LED6") (pin "C") (pinfunction "C_C") (pintype "passive"))
      (node (ref "Q1") (pin "3") (pinfunction "D_3") (pintype "passive"))
    )
    (net (code "62") (name "Net-(Q2-D)") (class "Default")
      (node (ref "Q2") (pin "3") (pinfunction "D_3") (pintype "passive"))
      (node (ref "R7") (pin "1") (pinfunction "1_1") (pintype "passive"))
    )
    (net (code "63") (name "Net-(Q3-B)") (class "Default")
      (node (ref "Q3") (pin "1") (pinfunction "B_1") (pintype "passive"))
      (node (ref "R18") (pin "1") (pinfunction "1_1") (pintype "passive"))
    )
    (net (code "64") (name "Net-(R16-Pad1)") (class "Default")
      (node (ref "R16") (pin "1") (pinfunction "1_1") (pintype "passive"))
      (node (ref "SJ4") (pin "1") (pinfunction "1_1") (pintype "passive"))
    )
    (net (code "65") (name "Net-(R17-Pad1)") (class "Default")
      (node (ref "R17") (pin "1") (pinfunction "1_1") (pintype "passive"))
      (node (ref "SJ5") (pin "1") (pinfunction "1_1") (pintype "passive"))
    )
    (net (code "66") (name "Net-(S5-1V8_OUT)") (class "Default")
      (node (ref "R18") (pin "2") (pinfunction "2_2") (pintype "passive"))
      (node (ref "S5") (pin "31") (pinfunction "1V8_OUT_31") (pintype "passive"))
    )
    (net (code "67") (name "Net-(S5-ADC1)") (class "Default")
      (node (ref "S5") (pin "11") (pinfunction "ADC1_11") (pintype "passive"))
      (node (ref "TP1") (pin "P$1") (pinfunction "1_P$1") (pintype "bidirectional"))
    )
    (net (code "68") (name "Net-(S5-ADC2_BATTEMP)") (class "Default")
      (node (ref "S5") (pin "12") (pinfunction "ADC2_BATTEMP_12") (pintype "passive"))
      (node (ref "TP2") (pin "P$1") (pinfunction "1_P$1") (pintype "bidirectional"))
    )
    (net (code "69") (name "Net-(S5-CHV_DRV)") (class "Default")
      (node (ref "S5") (pin "20") (pinfunction "CHV_DRV_20") (pintype "passive"))
      (node (ref "TP5") (pin "P$1") (pinfunction "1_P$1") (pintype "bidirectional"))
    )
    (net (code "70") (name "Net-(S5-EARN)") (class "Default")
      (node (ref "JP13") (pin "2") (pinfunction "2_2") (pintype "passive"))
      (node (ref "S4") (pin "1") (pinfunction "1_1") (pintype "bidirectional"))
      (node (ref "S5") (pin "50") (pinfunction "EARN_50") (pintype "passive"))
      (node (ref "SJ6") (pin "1") (pinfunction "1_1") (pintype "passive"))
    )
    (net (code "71") (name "Net-(S5-EARP)") (class "Default")
      (node (ref "JP13") (pin "1") (pinfunction "1_1") (pintype "passive"))
      (node (ref "S4") (pin "3") (pinfunction "3_3") (pintype "bidirectional"))
      (node (ref "S4") (pin "4") (pinfunction "4_4") (pintype "bidirectional"))
      (node (ref "S5") (pin "49") (pinfunction "EARP_49") (pintype "passive"))
    )
    (net (code "72") (name "Net-(S5-MIC1_N)") (class "Default")
      (node (ref "S5") (pin "44") (pinfunction "MIC1_N_44") (pintype "passive"))
      (node (ref "SJ3") (pin "2") (pinfunction "2_2") (pintype "passive"))
      (node (ref "SJ6") (pin "2") (pinfunction "2_2") (pintype "passive"))
    )
    (net (code "73") (name "Net-(S5-MIC1_P)") (class "Default")
      (node (ref "S4") (pin "2A") (pinfunction "2A_2A") (pintype "bidirectional"))
      (node (ref "S4") (pin "2B") (pinfunction "2B_2B") (pintype "bidirectional"))
      (node (ref "S5") (pin "43") (pinfunction "MIC1_P_43") (pintype "passive"))
      (node (ref "SJ2") (pin "2") (pinfunction "2_2") (pintype "passive"))
    )
    (net (code "74") (name "Net-(S5-RXD0)") (class "Default")
      (node (ref "R9") (pin "2") (pinfunction "2_2") (pintype "passive"))
      (node (ref "S5") (pin "17") (pinfunction "RXD0_17") (pintype "passive"))
    )
    (net (code "75") (name "Net-(S5-TXD0)") (class "Default")
      (node (ref "R8") (pin "2") (pinfunction "2_2") (pintype "passive"))
      (node (ref "S5") (pin "15") (pinfunction "TXD0_15") (pintype "passive"))
    )
    (net (code "76") (name "Net-(S5-VCHARGE18)") (class "Default")
      (node (ref "S5") (pin "18") (pinfunction "VCHARGE18_18") (pintype "passive"))
      (node (ref "TP3") (pin "P$1") (pinfunction "1_P$1") (pintype "bidirectional"))
    )
    (net (code "77") (name "Net-(S5-VCHARGE19)") (class "Default")
      (node (ref "S5") (pin "19") (pinfunction "VCHARGE19_19") (pintype "passive"))
      (node (ref "TP4") (pin "P$1") (pinfunction "1_P$1") (pintype "bidirectional"))
    )
    (net (code "78") (name "VCC") (class "Default")
      (node (ref "C10") (pin "2") (pinfunction "2_2") (pintype "passive"))
      (node (ref "C5") (pin "+") (pinfunction "+_+") (pintype "passive"))
      (node (ref "C6") (pin "+") (pinfunction "+_+") (pintype "passive"))
      (node (ref "IC3") (pin "3") (pinfunction "BAT_3") (pintype "bidirectional"))
      (node (ref "IC4") (pin "1") (pinfunction "IN_1") (pintype "input"))
      (node (ref "IC4") (pin "3") (pinfunction "~{EN}_3") (pintype "input"))
      (node (ref "J1") (pin "8") (pinfunction "8_8") (pintype "passive"))
      (node (ref "JP1") (pin "1") (pinfunction "1_1") (pintype "passive"))
      (node (ref "S2") (pin "POS") (pinfunction "POS_POS") (pintype "power_in"))
      (node (ref "S3") (pin "1") (pinfunction "1_1") (pintype "passive"))
      (node (ref "S5") (pin "26") (pinfunction "VBAT_26") (pintype "passive"))
      (node (ref "S5") (pin "27") (pinfunction "VBAT_27") (pintype "passive"))
      (node (ref "S5") (pin "28") (pinfunction "VBAT_28") (pintype "passive"))
      (node (ref "S5") (pin "29") (pinfunction "VBAT_29") (pintype "passive"))
      (node (ref "S5") (pin "30") (pinfunction "VBAT_30") (pintype "passive"))
    )
    (net (code "79") (name "unconnected-(IC1-PB0(PCINT8{slash}XCK0{slash}T0)-Pad40)") (class "Default")
      (node (ref "IC1") (pin "40") (pinfunction "PB0(PCINT8/XCK0/T0)_40") (pintype "bidirectional"))
    )
    (net (code "80") (name "unconnected-(IC1-PB1(PCINT9{slash}CLKO{slash}T1)-Pad41)") (class "Default")
      (node (ref "IC1") (pin "41") (pinfunction "PB1(PCINT9/CLKO/T1)_41") (pintype "bidirectional"))
    )
    (net (code "81") (name "unconnected-(IC2-CBUS0-Pad12)") (class "Default")
      (node (ref "IC2") (pin "12") (pinfunction "CBUS0_12") (pintype "bidirectional"))
    )
    (net (code "82") (name "unconnected-(IC2-CBUS3-Pad14)") (class "Default")
      (node (ref "IC2") (pin "14") (pinfunction "CBUS3_14") (pintype "bidirectional"))
    )
    (net (code "83") (name "unconnected-(IC2-~{CTS}-Pad4)") (class "Default")
      (node (ref "IC2") (pin "4") (pinfunction "~{CTS}_4") (pintype "bidirectional"))
    )
    (net (code "84") (name "unconnected-(IC4-NC{slash}FB-Pad4)") (class "Default")
      (node (ref "IC4") (pin "4") (pinfunction "NC/FB_4") (pintype "passive"))
    )
    (net (code "85") (name "unconnected-(J1-Pad1)") (class "Default")
      (node (ref "J1") (pin "1") (pinfunction "1_1") (pintype "passive"))
    )
    (net (code "86") (name "unconnected-(JP1-Pad4)") (class "Default")
      (node (ref "JP1") (pin "4") (pinfunction "4_4") (pintype "passive"))
    )
    (net (code "87") (name "unconnected-(P1-PadID)") (class "Default")
      (node (ref "P1") (pin "ID") (pinfunction "ID_ID") (pintype "bidirectional"))
    )
    (net (code "88") (name "unconnected-(S5-AUXOUTN-Pad48)") (class "Default")
      (node (ref "S5") (pin "48") (pinfunction "AUXOUTN_48") (pintype "passive"))
    )
    (net (code "89") (name "unconnected-(S5-AUXOUTP-Pad47)") (class "Default")
      (node (ref "S5") (pin "47") (pinfunction "AUXOUTP_47") (pintype "passive"))
    )
    (net (code "90") (name "unconnected-(S5-CHV_MAX-Pad40)") (class "Default")
      (node (ref "S5") (pin "40") (pinfunction "CHV_MAX_40") (pintype "passive"))
    )
    (net (code "91") (name "unconnected-(S5-DCD0-Pad39)") (class "Default")
      (node (ref "S5") (pin "39") (pinfunction "DCD0_39") (pintype "passive"))
    )
    (net (code "92") (name "unconnected-(S5-DTR0-Pad33)") (class "Default")
      (node (ref "S5") (pin "33") (pinfunction "DTR0_33") (pintype "passive"))
    )
    (net (code "93") (name "unconnected-(S5-IICSCL-Pad36)") (class "Default")
      (node (ref "S5") (pin "36") (pinfunction "IICSCL_36") (pintype "passive"))
    )
    (net (code "94") (name "unconnected-(S5-IICSDA-Pad38)") (class "Default")
      (node (ref "S5") (pin "38") (pinfunction "IICSDA_38") (pintype "passive"))
    )
    (net (code "95") (name "unconnected-(S5-MIC2_N-Pad46)") (class "Default")
      (node (ref "S5") (pin "46") (pinfunction "MIC2_N_46") (pintype "passive"))
    )
    (net (code "96") (name "unconnected-(S5-MIC2_P-Pad45)") (class "Default")
      (node (ref "S5") (pin "45") (pinfunction "MIC2_P_45") (pintype "passive"))
    )
    (net (code "97") (name "unconnected-(S5-PCMCLK-Pad9)") (class "Default")
      (node (ref "S5") (pin "9") (pinfunction "PCMCLK_9") (pintype "passive"))
    )
    (net (code "98") (name "unconnected-(S5-PCMDI-Pad7)") (class "Default")
      (node (ref "S5") (pin "7") (pinfunction "PCMDI_7") (pintype "passive"))
    )
    (net (code "99") (name "unconnected-(S5-PCMDO-Pad10)") (class "Default")
      (node (ref "S5") (pin "10") (pinfunction "PCMDO_10") (pintype "passive"))
    )
    (net (code "100") (name "unconnected-(S5-PCMFSO-Pad8)") (class "Default")
      (node (ref "S5") (pin "8") (pinfunction "PCMFSO_8") (pintype "passive"))
    )
    (net (code "101") (name "unconnected-(S5-RI0-Pad32)") (class "Default")
      (node (ref "S5") (pin "32") (pinfunction "RI0_32") (pintype "passive"))
    )
    (net (code "102") (name "unconnected-(S5-RTS0-Pad37)") (class "Default")
      (node (ref "S5") (pin "37") (pinfunction "RTS0_37") (pintype "passive"))
    )
    (net (code "103") (name "unconnected-(S5-RXD1-Pad16)") (class "Default")
      (node (ref "S5") (pin "16") (pinfunction "RXD1_16") (pintype "passive"))
    )
    (net (code "104") (name "unconnected-(S5-SIMCLK-Pad1)") (class "Default")
      (node (ref "S5") (pin "1") (pinfunction "SIMCLK_1") (pintype "passive"))
    )
    (net (code "105") (name "unconnected-(S5-SIMIO-Pad3)") (class "Default")
      (node (ref "S5") (pin "3") (pinfunction "SIMIO_3") (pintype "passive"))
    )
    (net (code "106") (name "unconnected-(S5-SIMRST-Pad4)") (class "Default")
      (node (ref "S5") (pin "4") (pinfunction "SIMRST_4") (pintype "passive"))
    )
    (net (code "107") (name "unconnected-(S5-SIMVDD-Pad2)") (class "Default")
      (node (ref "S5") (pin "2") (pinfunction "SIMVDD_2") (pintype "passive"))
    )
    (net (code "108") (name "unconnected-(S5-TXD1-Pad14)") (class "Default")
      (node (ref "S5") (pin "14") (pinfunction "TXD1_14") (pintype "passive"))
    )
  )
)
